# 1-Schematic_HackerCARD.net
KiCad netlist of a schematic drawn in EasyEDA
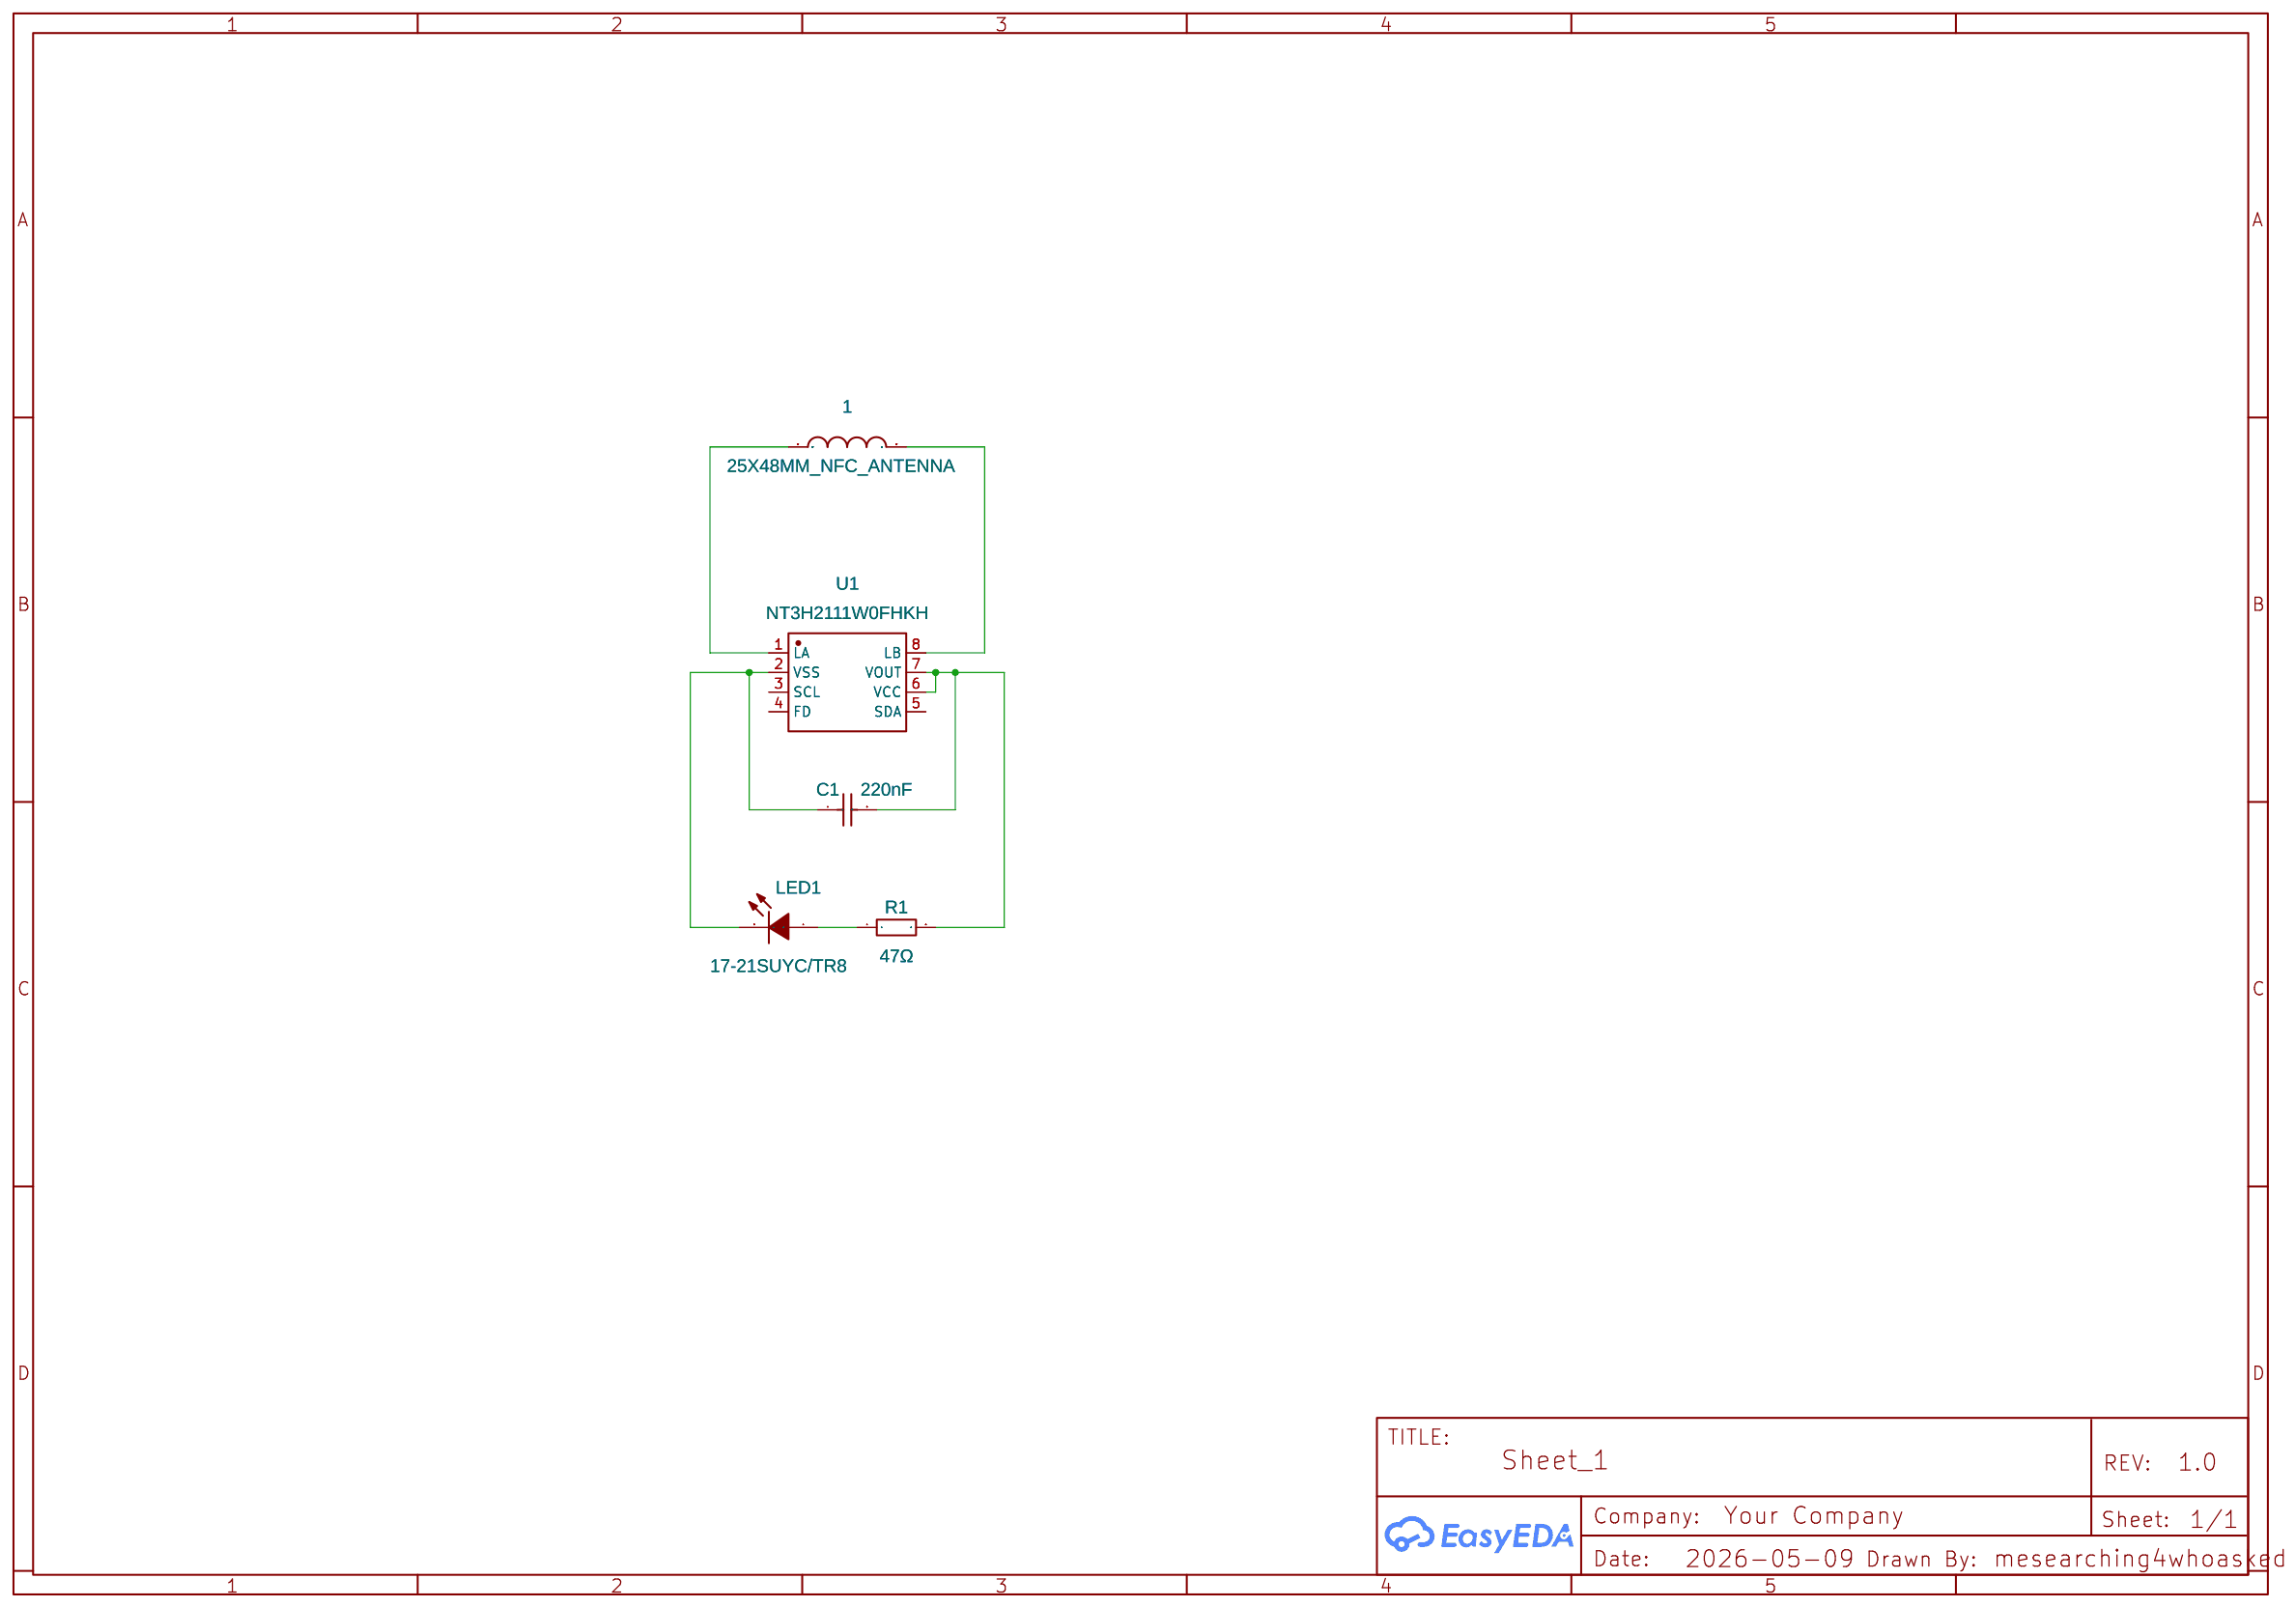
[diagram p0: schematic sheet]

(export (version "E")
  (design (tool "Eeschema 10.0.6"))
  (components
    (comp (ref "1") (value "25X48MM_NFC_ANTENNA") (libsource (lib "") (part "25X48MM_NFC_ANTENNA")))
    (comp (ref "C1")
      (value "220nF")
      (fields
        (field (name "Manufacturer Part") "CL10B224KA8NNNC")
        (field (name "Manufacturer") "SAMSUNG(三星)")
      )
      (libsource (lib "") (part "CL10B224KA8NNNC"))
    )
    (comp (ref "LED1")
      (value "17-21SUYC/TR8")
      (fields (field (name "Manufacturer Part") "KT-0805黄灯") (field (name "Manufacturer") "KENTO"))
      (libsource (lib "") (part "17-21SUYC/TR8"))
    )
    (comp (ref "R1")
      (value "47Ω")
      (fields
        (field (name "Manufacturer Part") "0603WAF470JT5E")
        (field (name "Manufacturer") "UNI-ROYAL(厚声)")
      )
      (libsource (lib "") (part "0603WAF470JT5E"))
    )
    (comp (ref "U1")
      (value "NT3H2111W0FHKH")
      (fields (field (name "Manufacturer") "NXP(恩智浦)"))
      (libsource (lib "") (part "NT3H2111W0FHKH"))
    )
  )
  (nets
    (net (code "1") (name "Net-(LED1-+)") (class "Default")
      (node (ref "LED1") (pin "1") (pinfunction "+_1") (pintype "unspecified"))
      (node (ref "R1") (pin "1") (pinfunction "1_1") (pintype "input"))
    )
    (net (code "2") (name "Net-(LED1--)") (class "Default")
      (node (ref "C1") (pin "1") (pinfunction "1_1") (pintype "input"))
      (node (ref "LED1") (pin "2") (pinfunction "-_2") (pintype "unspecified"))
      (node (ref "U1") (pin "2") (pinfunction "VSS_2") (pintype "unspecified"))
    )
    (net (code "3") (name "Net-(U1-LA)") (class "Default")
      (node (ref "1") (pin "P$1") (pinfunction "P$1_P$1") (pintype "bidirectional"))
      (node (ref "U1") (pin "1") (pinfunction "LA_1") (pintype "unspecified"))
    )
    (net (code "4") (name "Net-(U1-LB)") (class "Default")
      (node (ref "1") (pin "P$2") (pinfunction "P$2_P$2") (pintype "bidirectional"))
      (node (ref "U1") (pin "8") (pinfunction "LB_8") (pintype "unspecified"))
    )
    (net (code "5") (name "Net-(U1-VCC)") (class "Default")
      (node (ref "C1") (pin "2") (pinfunction "2_2") (pintype "input"))
      (node (ref "R1") (pin "2") (pinfunction "2_2") (pintype "input"))
      (node (ref "U1") (pin "6") (pinfunction "VCC_6") (pintype "unspecified"))
      (node (ref "U1") (pin "7") (pinfunction "VOUT_7") (pintype "unspecified"))
    )
    (net (code "6") (name "unconnected-(U1-FD-Pad4)") (class "Default")
      (node (ref "U1") (pin "4") (pinfunction "FD_4") (pintype "unspecified"))
    )
    (net (code "7") (name "unconnected-(U1-SCL-Pad3)") (class "Default")
      (node (ref "U1") (pin "3") (pinfunction "SCL_3") (pintype "unspecified"))
    )
    (net (code "8") (name "unconnected-(U1-SDA-Pad5)") (class "Default")
      (node (ref "U1") (pin "5") (pinfunction "SDA_5") (pintype "unspecified"))
    )
  )
)
